# MS5803-14BA_Breakout_v10.net
KiCad netlist of a schematic drawn in EAGLE
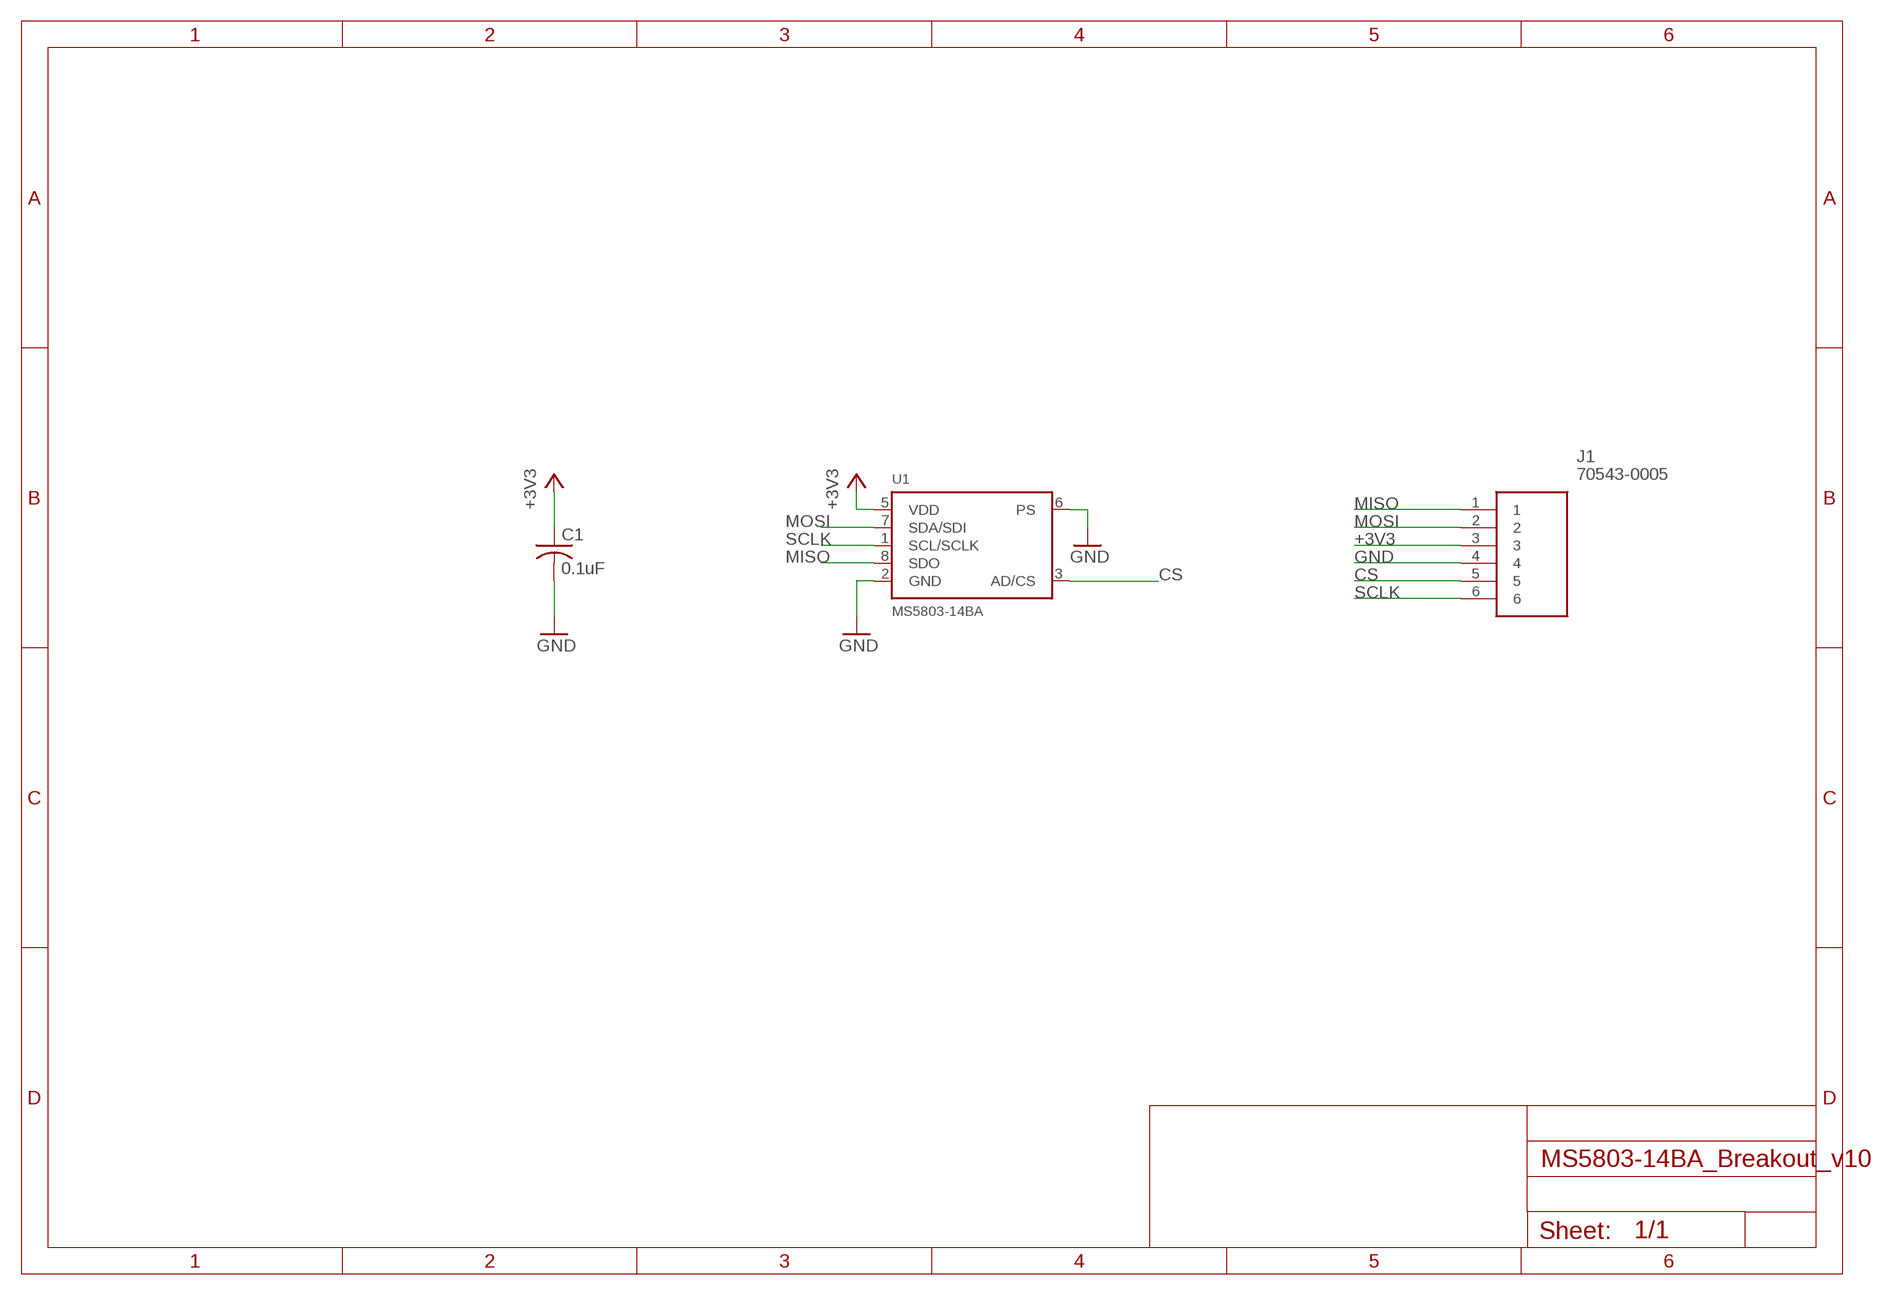
[diagram p0: schematic, sheet 1]

(export (version "E")
  (design (tool "Eeschema 10.0.6"))
  (components
    (comp (ref "C1")
      (value "0.1uF")
      (footprint "eagle-import:C1206")
      (libsource (lib "eagle-import") (part "C-USC1206"))
    )
    (comp (ref "J1")
      (value "70543-0005")
      (footprint "eagle-import:SHDR6W117P0X254_1X6_1779X508X1")
      (fields (field (name "MOUSER_PART_NUMBER") "538-70543-0005"))
      (libsource (lib "eagle-import") (part "70543-0005"))
    )
    (comp (ref "U1")
      (value "MS5803-14BA")
      (footprint "eagle-import:MS5803")
      (libsource (lib "eagle-import") (part "MS5803-14BA"))
    )
  )
  (nets
    (net (code "1") (name "+3V3") (class "Default")
      (node (ref "C1") (pin "1") (pinfunction "1_1") (pintype "passive"))
      (node (ref "J1") (pin "3") (pinfunction "3_3") (pintype "bidirectional"))
      (node (ref "U1") (pin "5") (pinfunction "VDD_5") (pintype "bidirectional"))
    )
    (net (code "2") (name "/CS") (class "Default")
      (node (ref "J1") (pin "5") (pinfunction "5_5") (pintype "bidirectional"))
      (node (ref "U1") (pin "3") (pinfunction "AD/CS_3") (pintype "bidirectional"))
    )
    (net (code "3") (name "/MISO") (class "Default")
      (node (ref "J1") (pin "1") (pinfunction "1_1") (pintype "bidirectional"))
      (node (ref "U1") (pin "8") (pinfunction "SDO_8") (pintype "bidirectional"))
    )
    (net (code "4") (name "/MOSI") (class "Default")
      (node (ref "J1") (pin "2") (pinfunction "2_2") (pintype "bidirectional"))
      (node (ref "U1") (pin "7") (pinfunction "SDA/SDI_7") (pintype "bidirectional"))
    )
    (net (code "5") (name "/SCLK") (class "Default")
      (node (ref "J1") (pin "6") (pinfunction "6_6") (pintype "bidirectional"))
      (node (ref "U1") (pin "1") (pinfunction "SCL/SCLK_1") (pintype "bidirectional"))
    )
    (net (code "6") (name "GND") (class "Default")
      (node (ref "C1") (pin "2") (pinfunction "2_2") (pintype "passive"))
      (node (ref "J1") (pin "4") (pinfunction "4_4") (pintype "bidirectional"))
      (node (ref "U1") (pin "2") (pinfunction "GND_2") (pintype "bidirectional"))
      (node (ref "U1") (pin "6") (pinfunction "PS_6") (pintype "bidirectional"))
    )
  )
)
